# HOST_RESET_SPNO.net
KiCad netlist of a schematic drawn in Altium Designer
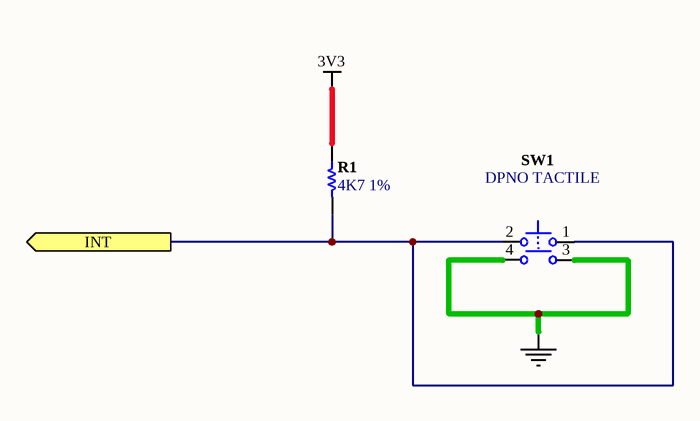
[diagram p0: HOST_RESET_SPNO.SCHDOC]

(export (version "E")
  (design (tool "Eeschema 10.0.6"))
  (components
    (comp (ref "R1")
      (value "4K7 1%")
      (footprint "RESC1005-STAR")
      (description "Resistor, 4K7 1% 0402 (1005)")
      (fields (field (name "TOLERANCE") "1 %"))
      (libsource (lib "altium-import") (part "root_0_mirrored_RES_"))
    )
    (comp (ref "SW1")
      (value "DPNO TACTILE")
      (footprint "IT-2175")
      (description "Switch, DPNO Push Button Through-Hole")
      (libsource (lib "AltiumDesignLibrary") (part "SWI-PB-DPNO"))
    )
  )
  (nets
    (net (code "1") (name "/INT") (class "Default")
      (node (ref "R1") (pin "2") (pinfunction "2_2") (pintype "passive"))
      (node (ref "SW1") (pin "1") (pinfunction "1_1") (pintype "passive"))
      (node (ref "SW1") (pin "2") (pinfunction "2_2") (pintype "passive"))
    )
    (net (code "2") (name "3V3") (class "Default")
      (node (ref "R1") (pin "1") (pinfunction "1_1") (pintype "passive"))
    )
    (net (code "3") (name "GND") (class "Default")
      (node (ref "SW1") (pin "3") (pinfunction "3_3") (pintype "passive"))
      (node (ref "SW1") (pin "4") (pinfunction "4_4") (pintype "passive"))
    )
  )
)
